# InducerNew_digital_only.net
KiCad netlist of a schematic drawn in Altium Designer
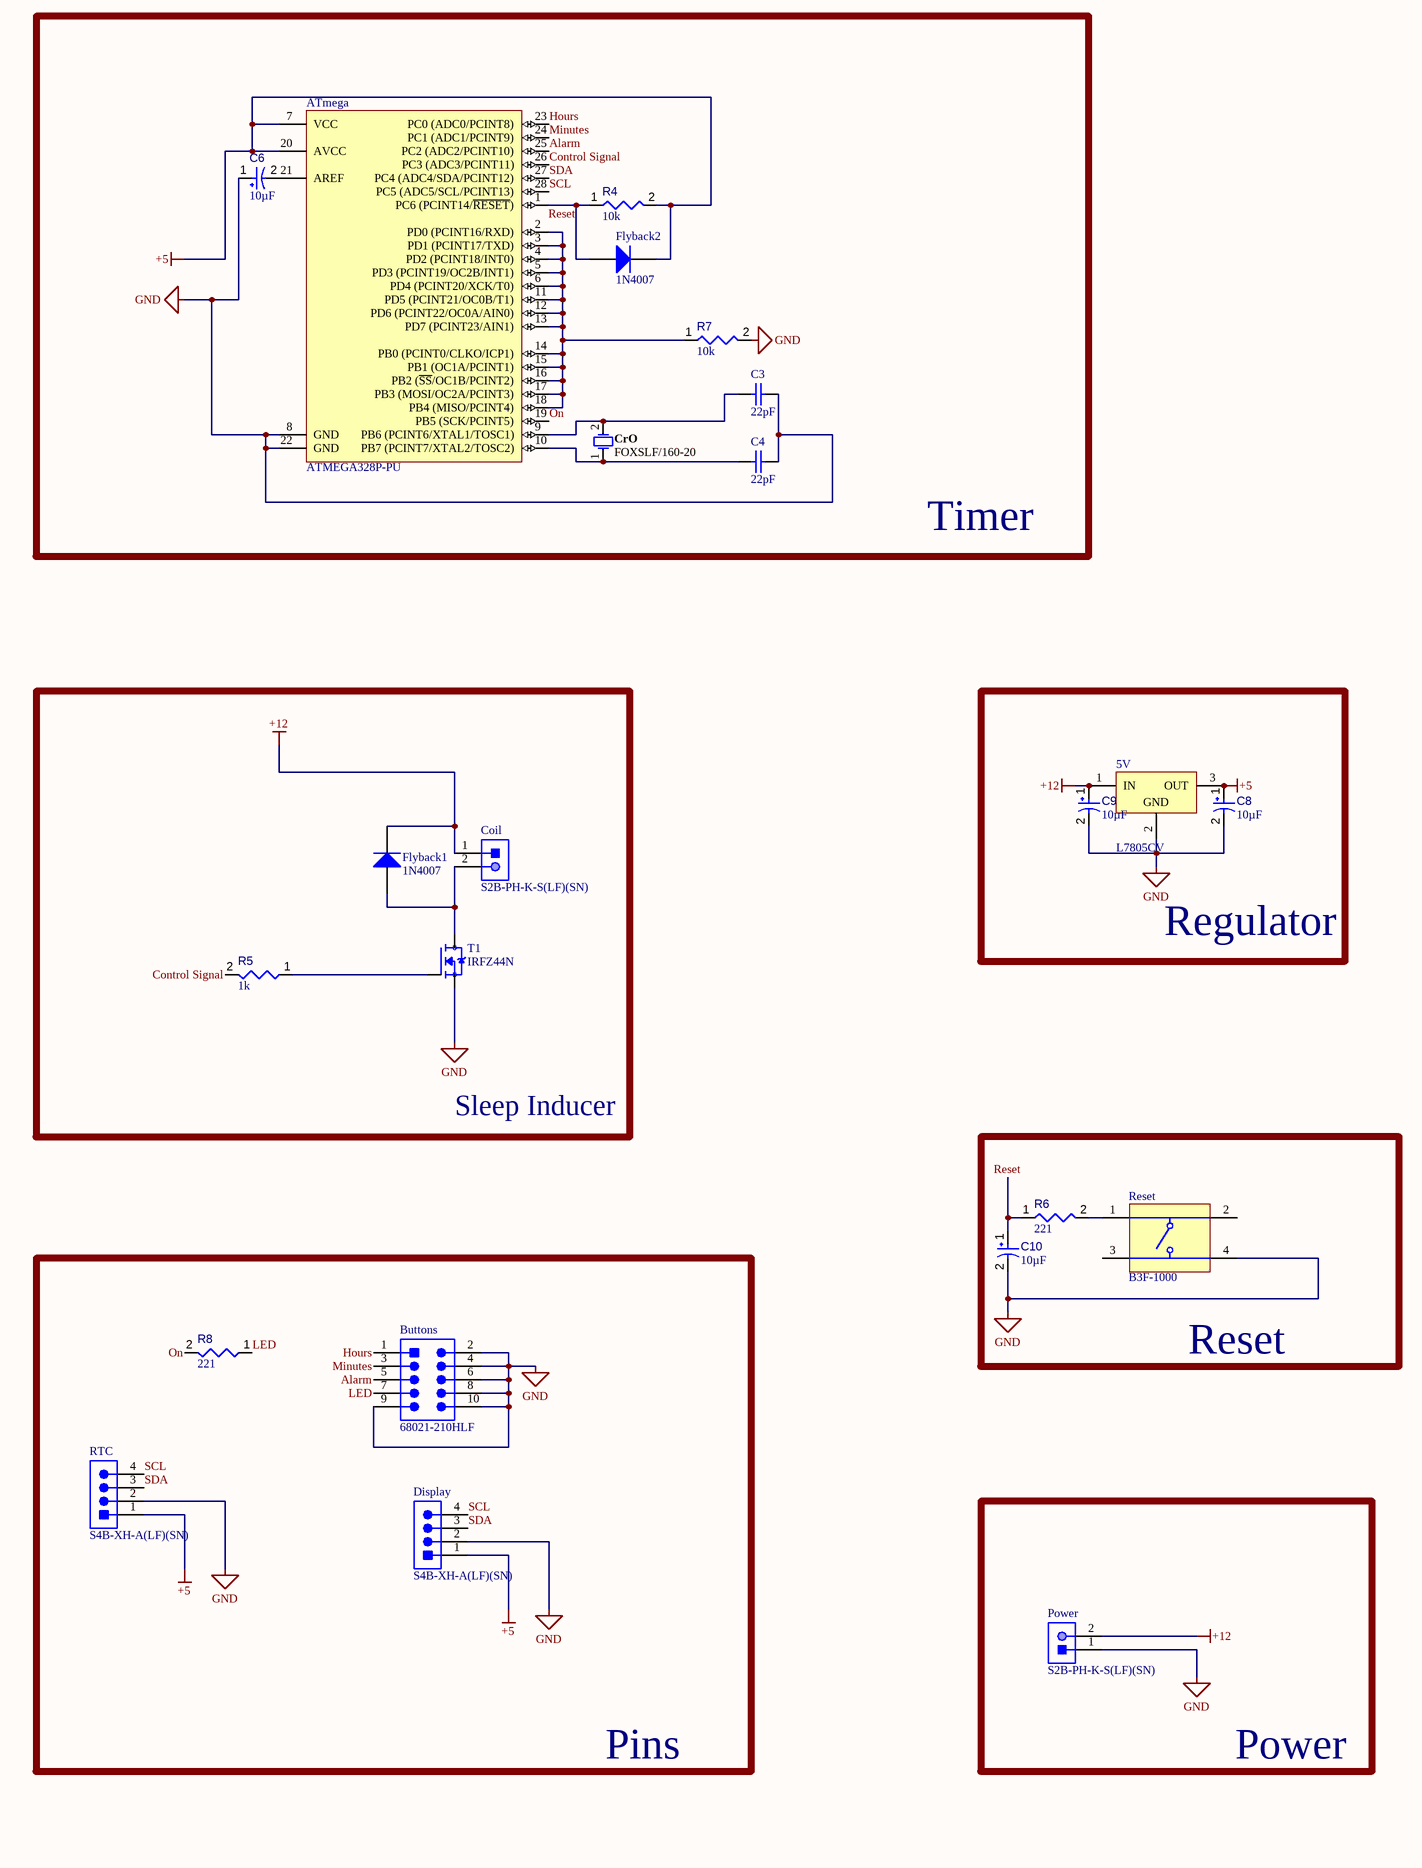
[diagram p0: InducerNew digital only.SchDoc, left]
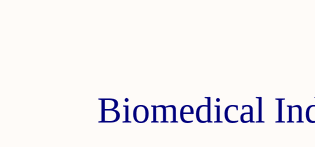
[diagram p1: InducerNew digital only.SchDoc, right]

(export (version "E")
  (design (tool "Eeschema 10.0.6"))
  (components
    (comp (ref "5V")
      (value "L7805CV")
      (footprint "TO220")
      (description "Positive Voltage Regulator IC, 1.5 A, 5 V, 0 to 125 degC, 3-Pin TO-220, RoHS, Tube")
      (fields (field (name "MANUFACTURER") "STMicroelectronics"))
      (libsource (lib "University of Moratuwa") (part "PM-REG-L4940-SIL3"))
    )
    (comp (ref "ATmega")
      (value "ATMEGA328P-PU")
      (footprint "ATML-28P3")
      (fields (field (name "MANUFACTURER") "Atmel"))
      (libsource (lib "University of Moratuwa") (part "MC-8B-ATM48-IL28"))
    )
    (comp (ref "Buttons")
      (value "68021-210HLF")
      (footprint "FCI-68021-210HLF-10_V")
      (description "Male Header, Pitch 2.54 mm, 2 x 5 Position, Height 4.83 mm, Tail Length 3.05 mm, Bulk")
      (fields (field (name "MANUFACTURER") "FCI Electronics"))
      (libsource (lib "University of Moratuwa") (part "CN-2P-M-R10"))
    )
    (comp (ref "C3")
      (value "22pF")
      (footprint "KEMT-C315-THT-2")
      (description "Capacitor, Ceramic, 22 pF, +/-10 %, 100 V, -55 to 125 degC, 2-Pin THD, RoHS, Bulk")
      (libsource (lib "Altium Content Vault") (part "CAP-NP-2"))
    )
    (comp (ref "C4")
      (value "22pF")
      (footprint "KEMT-C315-THT-2")
      (description "Capacitor, Ceramic, 22 pF, +/-10 %, 100 V, -55 to 125 degC, 2-Pin THD, RoHS, Bulk")
      (libsource (lib "Altium Content Vault") (part "CAP-NP-2"))
    )
    (comp (ref "C6")
      (value "10µF")
      (footprint "CAPPR55-200-1100X500X1200")
      (description "Aluminum Electrolytic Capacitor, 10 uF, +/- 20%, 50 V, -40 to 85 degC, 2-Pin THD, RoHS, Bulk")
      (fields (field (name "MANUFACTURER") "Panasonic") (field (name "TOLERANCE") "20%"))
      (libsource (lib "University of Moratuwa") (part "CAP-P-2"))
    )
    (comp (ref "C8")
      (value "10µF")
      (footprint "CAPPR55-200-1100X500X1200")
      (description "Aluminum Electrolytic Capacitor, 10 uF, +/- 20%, 50 V, -40 to 85 degC, 2-Pin THD, RoHS, Bulk")
      (fields (field (name "MANUFACTURER") "Panasonic") (field (name "TOLERANCE") "20%"))
      (libsource (lib "") (part "CAP-P-2_1"))
    )
    (comp (ref "C9")
      (value "10µF")
      (footprint "CAPPR55-200-1100X500X1200")
      (description "Aluminum Electrolytic Capacitor, 10 uF, +/- 20%, 50 V, -40 to 85 degC, 2-Pin THD, RoHS, Bulk")
      (fields (field (name "MANUFACTURER") "Panasonic") (field (name "TOLERANCE") "20%"))
      (libsource (lib "") (part "CAP-P-2_1"))
    )
    (comp (ref "C10")
      (value "10µF")
      (footprint "CAPPR55-200-1100X500X1200")
      (description "Aluminum Electrolytic Capacitor, 10 uF, +/- 20%, 50 V, -40 to 85 degC, 2-Pin THD, RoHS, Bulk")
      (fields (field (name "MANUFACTURER") "Panasonic") (field (name "TOLERANCE") "20%"))
      (libsource (lib "") (part "CAP-P-2_1"))
    )
    (comp (ref "Coil")
      (value "S2B-PH-K-S(LF)(SN)")
      (footprint "JST-S2B-PH-K-S_V")
      (fields (field (name "MANUFACTURER") "Japan Solderless Terminals"))
      (libsource (lib "") (part "CN-1P-M-R2_1"))
    )
    (comp (ref "CrO")
      (value "FOXSLF/160-20")
      (footprint "FOX-FOXSLF160-20")
      (description "Resistance Weld Thru-Hole Crystal, 16 MHz, -20 to 70 degC, 2-Pin THD, RoHS, Bulk")
      (fields (field (name "TOLERANCE") "1%"))
      (libsource (lib "Altium Content Vault") (part "XTAL-1-2-2"))
    )
    (comp (ref "Display")
      (value "S4B-XH-A(LF)(SN)")
      (footprint "JST-S4B-XH-A(LF)(SN)_V")
      (fields (field (name "MANUFACTURER") "JST"))
      (libsource (lib "University of Moratuwa") (part "CN-1P-M-R4"))
    )
    (comp (ref "Flyback1")
      (value "1N4007")
      (footprint "FAIR-DO-41-2")
      (description "General Purpose Rectifier, 1.1 V, 1.0 A, -55 to 175 degC, 2-Pin DO-41, RoHS, Tape and Reel")
      (fields (field (name "MANUFACTURER") "Fairchild"))
      (libsource (lib "University of Moratuwa") (part "KESE-D_K1A2-2"))
    )
    (comp (ref "Flyback2")
      (value "1N4007")
      (footprint "FAIR-DO-41-2")
      (description "General Purpose Rectifier, 1.1 V, 1.0 A, -55 to 175 degC, 2-Pin DO-41, RoHS, Tape and Reel")
      (fields (field (name "MANUFACTURER") "Fairchild"))
      (libsource (lib "University of Moratuwa") (part "KESE-D_K1A2-2"))
    )
    (comp (ref "Power")
      (value "S2B-PH-K-S(LF)(SN)")
      (footprint "JST-S2B-PH-K-S_V")
      (fields (field (name "MANUFACTURER") "Japan Solderless Terminals"))
      (libsource (lib "University of Moratuwa") (part "CN-1P-M-R2"))
    )
    (comp (ref "R4")
      (value "10k")
      (footprint "RESA60-630X240")
      (description "Axial Resistor, 10 KOhm, +/- 1%, 0.25 W, -55 to 155 degC, 2-Pin THD, RoHS, Bulk")
      (fields (field (name "TOLERANCE") "1%") (field (name "POWER") "250mW"))
      (libsource (lib "University of Moratuwa") (part "RES-2"))
    )
    (comp (ref "R5")
      (value "1k")
      (footprint "RESA60-630X240")
      (description "Axial Resistor, 1 KOhm, +/- 1%, 250 mW, -55 to 155 degC, 2-Pin THD, RoHS, Bulk")
      (fields (field (name "TOLERANCE") "1%") (field (name "POWER") "250mW"))
      (libsource (lib "University of Moratuwa") (part "RES-2"))
    )
    (comp (ref "R6")
      (value "221")
      (footprint "RESA60-630X240")
      (description "Axial Resistor, 221 Ohm, +/- 1%, 250 mW, -55 to 155 degC, 2-Pin THD, RoHS, Bulk")
      (fields (field (name "POWER") "250mW") (field (name "TOLERANCE") "1%"))
      (libsource (lib "University of Moratuwa") (part "RES-2"))
    )
    (comp (ref "R7")
      (value "10k")
      (footprint "RESA60-630X240")
      (description "Axial Resistor, 10 KOhm, +/- 1%, 0.25 W, -55 to 155 degC, 2-Pin THD, RoHS, Bulk")
      (fields (field (name "TOLERANCE") "1%") (field (name "POWER") "250mW"))
      (libsource (lib "University of Moratuwa") (part "RES-2"))
    )
    (comp (ref "R8")
      (value "221")
      (footprint "RESA60-630X240")
      (description "Axial Resistor, 221 Ohm, +/- 1%, 250 mW, -55 to 155 degC, 2-Pin THD, RoHS, Bulk")
      (fields (field (name "POWER") "250mW") (field (name "TOLERANCE") "1%"))
      (libsource (lib "University of Moratuwa") (part "RES-2"))
    )
    (comp (ref "Reset")
      (value "B3F-1000")
      (footprint "OMRON-B3F-1000-4_V")
      (description "Tactile Switch, SPST-NO, 0.05 A, 24 V, -25 to 70 degC, 4-Pin THD, RoHS, Bulk")
      (fields (field (name "MANUFACTURER") "Omron Electronic Components"))
      (libsource (lib "University of Moratuwa") (part "SW-SPST-4_A"))
    )
    (comp (ref "RTC")
      (value "S4B-XH-A(LF)(SN)")
      (footprint "JST-S4B-XH-A(LF)(SN)_V")
      (fields (field (name "MANUFACTURER") "JST"))
      (libsource (lib "University of Moratuwa") (part "CN-1P-M-R4"))
    )
    (comp (ref "T1")
      (value "IRFZ44N")
      (footprint "TO254P1016X419X2286-3")
      (description "N-Channel 55 V 49A (Tc) 94W (Tc) Through Hole TO-220AB")
      (fields (field (name "MF") "Infineon Technologies"))
      (libsource (lib "University of Moratuwa") (part "IRFZ44N"))
    )
  )
  (nets
    (net (code "1") (name "+5") (class "Default")
      (node (ref "5V") (pin "3") (pinfunction "OUT_3") (pintype "power_in"))
      (node (ref "ATmega") (pin "20") (pinfunction "AVCC_20") (pintype "power_in"))
      (node (ref "ATmega") (pin "7") (pinfunction "VCC_7") (pintype "power_in"))
      (node (ref "C8") (pin "1") (pinfunction "1_1") (pintype "passive"))
      (node (ref "Display") (pin "1") (pinfunction "1_1") (pintype "passive"))
      (node (ref "Flyback2") (pin "1") (pinfunction "K_1") (pintype "passive"))
      (node (ref "R4") (pin "2") (pinfunction "2_2") (pintype "passive"))
      (node (ref "RTC") (pin "1") (pinfunction "1_1") (pintype "passive"))
    )
    (net (code "2") (name "+12") (class "Default")
      (node (ref "5V") (pin "1") (pinfunction "IN_1") (pintype "power_in"))
      (node (ref "C9") (pin "1") (pinfunction "1_1") (pintype "passive"))
      (node (ref "Coil") (pin "1") (pinfunction "1_1") (pintype "passive"))
      (node (ref "Flyback1") (pin "1") (pinfunction "K_1") (pintype "passive"))
      (node (ref "Power") (pin "2") (pinfunction "2_2") (pintype "passive"))
    )
    (net (code "3") (name "/Alarm") (class "Default")
      (node (ref "ATmega") (pin "25") (pinfunction "PC2_(ADC2/PCINT10)_25") (pintype "bidirectional"))
      (node (ref "Buttons") (pin "5") (pinfunction "5_5") (pintype "passive"))
    )
    (net (code "4") (name "/Control Signal") (class "Default")
      (node (ref "ATmega") (pin "26") (pinfunction "PC3_(ADC3/PCINT11)_26") (pintype "bidirectional"))
      (node (ref "R5") (pin "2") (pinfunction "2_2") (pintype "passive"))
    )
    (net (code "5") (name "/Hours") (class "Default")
      (node (ref "ATmega") (pin "23") (pinfunction "PC0_(ADC0/PCINT8)_23") (pintype "bidirectional"))
      (node (ref "Buttons") (pin "1") (pinfunction "1_1") (pintype "passive"))
    )
    (net (code "6") (name "/LED") (class "Default")
      (node (ref "Buttons") (pin "7") (pinfunction "7_7") (pintype "passive"))
      (node (ref "R8") (pin "1") (pinfunction "1_1") (pintype "passive"))
    )
    (net (code "7") (name "/Minutes") (class "Default")
      (node (ref "ATmega") (pin "24") (pinfunction "PC1_(ADC1/PCINT9)_24") (pintype "bidirectional"))
      (node (ref "Buttons") (pin "3") (pinfunction "3_3") (pintype "passive"))
    )
    (net (code "8") (name "/On") (class "Default")
      (node (ref "ATmega") (pin "19") (pinfunction "PB5_(SCK/PCINT5)_19") (pintype "bidirectional"))
      (node (ref "R8") (pin "2") (pinfunction "2_2") (pintype "passive"))
    )
    (net (code "9") (name "/Reset") (class "Default")
      (node (ref "ATmega") (pin "1") (pinfunction "PC6_(PCINT14/~{RESET})_1") (pintype "bidirectional"))
      (node (ref "C10") (pin "1") (pinfunction "1_1") (pintype "passive"))
      (node (ref "Flyback2") (pin "2") (pinfunction "A_2") (pintype "passive"))
      (node (ref "R4") (pin "1") (pinfunction "1_1") (pintype "passive"))
      (node (ref "R6") (pin "1") (pinfunction "1_1") (pintype "passive"))
    )
    (net (code "10") (name "/SCL") (class "Default")
      (node (ref "ATmega") (pin "28") (pinfunction "PC5_(ADC5/SCL/PCINT13)_28") (pintype "bidirectional"))
      (node (ref "Display") (pin "4") (pinfunction "4_4") (pintype "passive"))
      (node (ref "RTC") (pin "4") (pinfunction "4_4") (pintype "passive"))
    )
    (net (code "11") (name "/SDA") (class "Default")
      (node (ref "ATmega") (pin "27") (pinfunction "PC4_(ADC4/SDA/PCINT12)_27") (pintype "bidirectional"))
      (node (ref "Display") (pin "3") (pinfunction "3_3") (pintype "passive"))
      (node (ref "RTC") (pin "3") (pinfunction "3_3") (pintype "passive"))
    )
    (net (code "12") (name "GND") (class "Default")
      (node (ref "5V") (pin "2") (pinfunction "GND_2") (pintype "power_in"))
      (node (ref "ATmega") (pin "22") (pinfunction "GND_22") (pintype "power_in"))
      (node (ref "ATmega") (pin "8") (pinfunction "GND_8") (pintype "power_in"))
      (node (ref "Buttons") (pin "10") (pinfunction "10_10") (pintype "passive"))
      (node (ref "Buttons") (pin "2") (pinfunction "2_2") (pintype "passive"))
      (node (ref "Buttons") (pin "4") (pinfunction "4_4") (pintype "passive"))
      (node (ref "Buttons") (pin "6") (pinfunction "6_6") (pintype "passive"))
      (node (ref "Buttons") (pin "8") (pinfunction "8_8") (pintype "passive"))
      (node (ref "Buttons") (pin "9") (pinfunction "9_9") (pintype "passive"))
      (node (ref "C10") (pin "2") (pinfunction "2_2") (pintype "passive"))
      (node (ref "C3") (pin "2") (pinfunction "2_2") (pintype "passive"))
      (node (ref "C4") (pin "2") (pinfunction "2_2") (pintype "passive"))
      (node (ref "C6") (pin "1") (pinfunction "1_1") (pintype "passive"))
      (node (ref "C8") (pin "2") (pinfunction "2_2") (pintype "passive"))
      (node (ref "C9") (pin "2") (pinfunction "2_2") (pintype "passive"))
      (node (ref "Display") (pin "2") (pinfunction "2_2") (pintype "passive"))
      (node (ref "Power") (pin "1") (pinfunction "1_1") (pintype "passive"))
      (node (ref "R7") (pin "2") (pinfunction "2_2") (pintype "passive"))
      (node (ref "RTC") (pin "2") (pinfunction "2_2") (pintype "passive"))
      (node (ref "Reset") (pin "4") (pinfunction "4_4") (pintype "passive"))
      (node (ref "T1") (pin "3") (pinfunction "S_3") (pintype "passive"))
    )
    (net (code "13") (name "Net-(ATmega-AREF)") (class "Default")
      (node (ref "ATmega") (pin "21") (pinfunction "AREF_21") (pintype "power_in"))
      (node (ref "C6") (pin "2") (pinfunction "2_2") (pintype "passive"))
    )
    (net (code "14") (name "Net-(ATmega-PB0_(PCINT0{slash}CLKO{slash}ICP1))") (class "Default")
      (node (ref "ATmega") (pin "11") (pinfunction "PD5_(PCINT21/OC0B/T1)_11") (pintype "bidirectional"))
      (node (ref "ATmega") (pin "12") (pinfunction "PD6_(PCINT22/OC0A/AIN0)_12") (pintype "bidirectional"))
      (node (ref "ATmega") (pin "13") (pinfunction "PD7_(PCINT23/AIN1)_13") (pintype "bidirectional"))
      (node (ref "ATmega") (pin "14") (pinfunction "PB0_(PCINT0/CLKO/ICP1)_14") (pintype "bidirectional"))
      (node (ref "ATmega") (pin "15") (pinfunction "PB1_(OC1A/PCINT1)_15") (pintype "bidirectional"))
      (node (ref "ATmega") (pin "16") (pinfunction "PB2_(~{SS}/OC1B/PCINT2)_16") (pintype "bidirectional"))
      (node (ref "ATmega") (pin "17") (pinfunction "PB3_(MOSI/OC2A/PCINT3)_17") (pintype "bidirectional"))
      (node (ref "ATmega") (pin "18") (pinfunction "PB4_(MISO/PCINT4)_18") (pintype "bidirectional"))
      (node (ref "ATmega") (pin "2") (pinfunction "PD0_(PCINT16/RXD)_2") (pintype "bidirectional"))
      (node (ref "ATmega") (pin "3") (pinfunction "PD1_(PCINT17/TXD)_3") (pintype "bidirectional"))
      (node (ref "ATmega") (pin "4") (pinfunction "PD2_(PCINT18/INT0)_4") (pintype "bidirectional"))
      (node (ref "ATmega") (pin "5") (pinfunction "PD3_(PCINT19/OC2B/INT1)_5") (pintype "bidirectional"))
      (node (ref "ATmega") (pin "6") (pinfunction "PD4_(PCINT20/XCK/T0)_6") (pintype "bidirectional"))
      (node (ref "R7") (pin "1") (pinfunction "1_1") (pintype "passive"))
    )
    (net (code "15") (name "Net-(ATmega-PB6_(PCINT6{slash}XTAL1{slash}TOSC1))") (class "Default")
      (node (ref "ATmega") (pin "9") (pinfunction "PB6_(PCINT6/XTAL1/TOSC1)_9") (pintype "bidirectional"))
      (node (ref "C3") (pin "1") (pinfunction "1_1") (pintype "passive"))
      (node (ref "CrO") (pin "2") (pinfunction "2_2") (pintype "passive"))
    )
    (net (code "16") (name "Net-(ATmega-PB7_(PCINT7{slash}XTAL2{slash}TOSC2))") (class "Default")
      (node (ref "ATmega") (pin "10") (pinfunction "PB7_(PCINT7/XTAL2/TOSC2)_10") (pintype "bidirectional"))
      (node (ref "C4") (pin "1") (pinfunction "1_1") (pintype "passive"))
      (node (ref "CrO") (pin "1") (pinfunction "1_1") (pintype "passive"))
    )
    (net (code "17") (name "Net-(Flyback1-A)") (class "Default")
      (node (ref "Coil") (pin "2") (pinfunction "2_2") (pintype "passive"))
      (node (ref "Flyback1") (pin "2") (pinfunction "A_2") (pintype "passive"))
      (node (ref "T1") (pin "2") (pinfunction "D_2") (pintype "passive"))
    )
    (net (code "18") (name "Net-(R6-Pad2)") (class "Default")
      (node (ref "R6") (pin "2") (pinfunction "2_2") (pintype "passive"))
      (node (ref "Reset") (pin "1") (pinfunction "1_1") (pintype "passive"))
    )
    (net (code "19") (name "Net-(T1-G)") (class "Default")
      (node (ref "R5") (pin "1") (pinfunction "1_1") (pintype "passive"))
      (node (ref "T1") (pin "1") (pinfunction "G_1") (pintype "passive"))
    )
    (net (code "20") (name "unconnected-(Reset-Pad2)") (class "Default")
      (node (ref "Reset") (pin "2") (pinfunction "2_2") (pintype "passive"))
    )
    (net (code "21") (name "unconnected-(Reset-Pad3)") (class "Default")
      (node (ref "Reset") (pin "3") (pinfunction "3_3") (pintype "passive"))
    )
  )
)
